# Mic-Breakout_v10.net
KiCad netlist of a schematic drawn in EAGLE
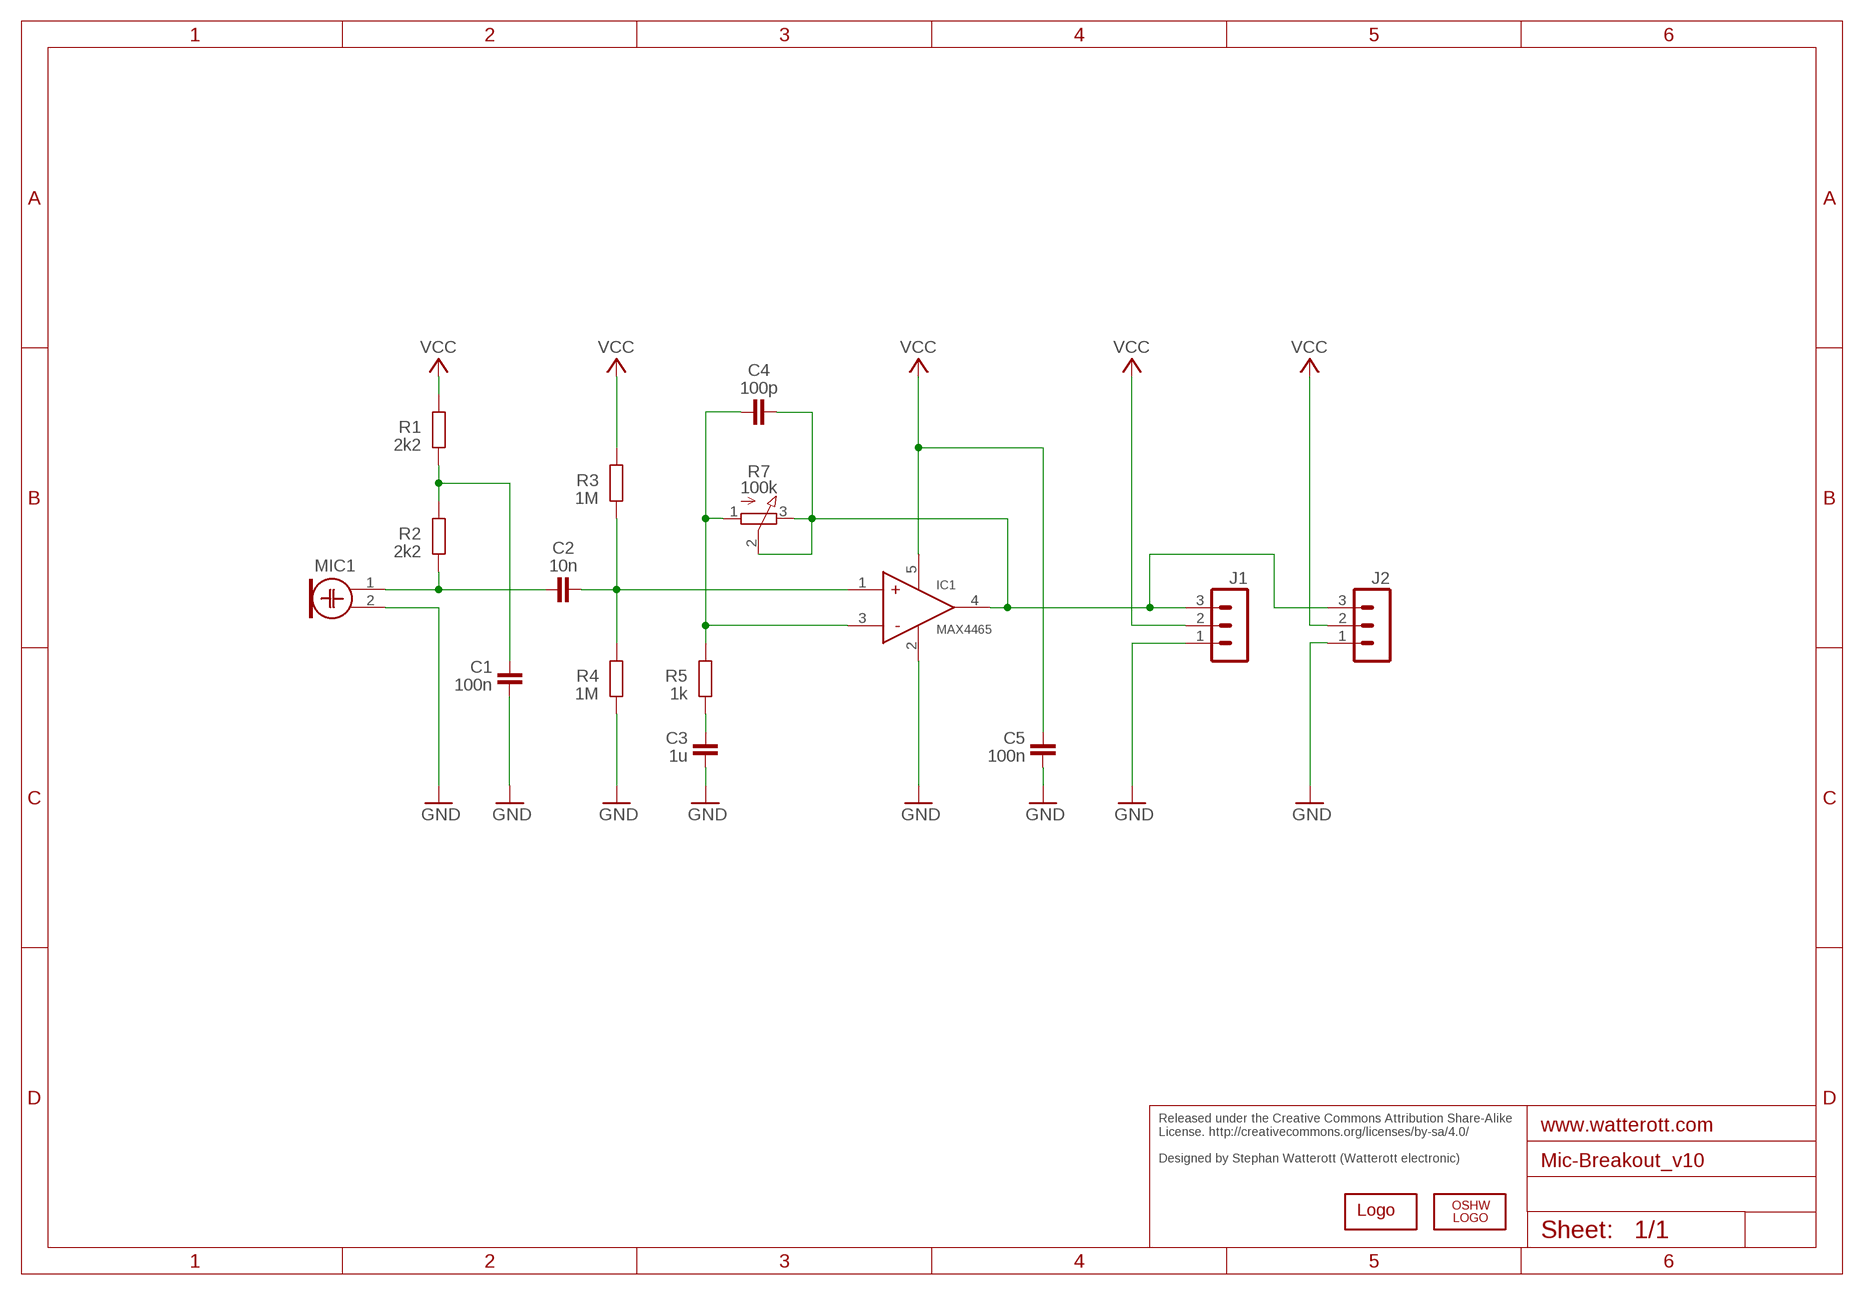
[diagram p0: schematic, sheet 1]

(export (version "E")
  (design (tool "Eeschema 10.0.6"))
  (components
    (comp (ref "C1")
      (value "100n")
      (footprint "eagle-import:R0402")
      (libsource (lib "eagle-import") (part "CAPACITOR-C0402"))
    )
    (comp (ref "C2")
      (value "10n")
      (footprint "eagle-import:R0402")
      (libsource (lib "eagle-import") (part "CAPACITOR-C0402"))
    )
    (comp (ref "C3")
      (value "1u")
      (footprint "eagle-import:R0402")
      (libsource (lib "eagle-import") (part "CAPACITOR-C0402"))
    )
    (comp (ref "C4")
      (value "100p")
      (footprint "eagle-import:R0402")
      (libsource (lib "eagle-import") (part "CAPACITOR-C0402"))
    )
    (comp (ref "C5")
      (value "100n")
      (footprint "eagle-import:R0402")
      (libsource (lib "eagle-import") (part "CAPACITOR-C0402"))
    )
    (comp (ref "IC1")
      (value "MAX4465")
      (footprint "eagle-import:SOT23-5")
      (libsource (lib "eagle-import") (part "MAX4465"))
    )
    (comp (ref "J1")
      (value "MA03-1")
      (footprint "eagle-import:MA03-1")
      (libsource (lib "eagle-import") (part "MA03-1"))
    )
    (comp (ref "J2")
      (value "JST_PH_3S3B-PH-SM4-TB")
      (footprint "eagle-import:JST_S3B-PH-SM4-TB")
      (libsource (lib "eagle-import") (part "JST_PH_3S3B-PH-SM4-TB"))
    )
    (comp (ref "LOGO1")
      (value "LOGO-S_PLACE_M")
      (footprint "eagle-import:SPARK_TPLACE_M")
      (libsource (lib "eagle-import") (part "LOGO-S_PLACE_M"))
    )
    (comp (ref "LOGO2")
      (value "OSHW_LOGOX0100")
      (footprint "eagle-import:OSHW_6X100")
      (libsource (lib "eagle-import") (part "OSHW_LOGOX0100"))
    )
    (comp (ref "MIC1")
      (value "CMA-4544PF")
      (footprint "eagle-import:CMA-4544PF")
      (libsource (lib "eagle-import") (part "CMA-4544PF"))
    )
    (comp (ref "R1")
      (value "2k2")
      (footprint "eagle-import:R0402")
      (libsource (lib "eagle-import") (part "RESISTOR-R0402"))
    )
    (comp (ref "R2")
      (value "2k2")
      (footprint "eagle-import:R0402")
      (libsource (lib "eagle-import") (part "RESISTOR-R0402"))
    )
    (comp (ref "R3")
      (value "1M")
      (footprint "eagle-import:R0402")
      (libsource (lib "eagle-import") (part "RESISTOR-R0402"))
    )
    (comp (ref "R4")
      (value "1M")
      (footprint "eagle-import:R0402")
      (libsource (lib "eagle-import") (part "RESISTOR-R0402"))
    )
    (comp (ref "R5")
      (value "1k")
      (footprint "eagle-import:R0402")
      (libsource (lib "eagle-import") (part "RESISTOR-R0402"))
    )
    (comp (ref "R7")
      (value "100k")
      (footprint "eagle-import:POT_EVM3Y")
      (libsource (lib "eagle-import") (part "POTEVM3Y"))
    )
  )
  (nets
    (net (code "1") (name "GND") (class "Default")
      (node (ref "C1") (pin "1") (pinfunction "1_1") (pintype "passive"))
      (node (ref "C3") (pin "1") (pinfunction "1_1") (pintype "passive"))
      (node (ref "C5") (pin "1") (pinfunction "1_1") (pintype "passive"))
      (node (ref "IC1") (pin "2") (pinfunction "GND_2") (pintype "power_in"))
      (node (ref "J1") (pin "1") (pinfunction "1_1") (pintype "passive"))
      (node (ref "J2") (pin "1") (pinfunction "1_1") (pintype "passive"))
      (node (ref "MIC1") (pin "2") (pinfunction "2_2") (pintype "passive"))
      (node (ref "R4") (pin "1") (pinfunction "1_1") (pintype "passive"))
    )
    (net (code "2") (name "Net-(C1-Pad2)") (class "Default")
      (node (ref "C1") (pin "2") (pinfunction "2_2") (pintype "passive"))
      (node (ref "R1") (pin "1") (pinfunction "1_1") (pintype "passive"))
      (node (ref "R2") (pin "2") (pinfunction "2_2") (pintype "passive"))
    )
    (net (code "3") (name "Net-(C2-Pad1)") (class "Default")
      (node (ref "C2") (pin "1") (pinfunction "1_1") (pintype "passive"))
      (node (ref "MIC1") (pin "1") (pinfunction "1_1") (pintype "passive"))
      (node (ref "R2") (pin "1") (pinfunction "1_1") (pintype "passive"))
    )
    (net (code "4") (name "Net-(C3-Pad2)") (class "Default")
      (node (ref "C3") (pin "2") (pinfunction "2_2") (pintype "passive"))
      (node (ref "R5") (pin "1") (pinfunction "1_1") (pintype "passive"))
    )
    (net (code "5") (name "Net-(IC1-+)") (class "Default")
      (node (ref "C2") (pin "2") (pinfunction "2_2") (pintype "passive"))
      (node (ref "IC1") (pin "1") (pinfunction "+_1") (pintype "input"))
      (node (ref "R3") (pin "1") (pinfunction "1_1") (pintype "passive"))
      (node (ref "R4") (pin "2") (pinfunction "2_2") (pintype "passive"))
    )
    (net (code "6") (name "Net-(IC1--)") (class "Default")
      (node (ref "C4") (pin "2") (pinfunction "2_2") (pintype "passive"))
      (node (ref "IC1") (pin "3") (pinfunction "-_3") (pintype "input"))
      (node (ref "R5") (pin "2") (pinfunction "2_2") (pintype "passive"))
      (node (ref "R7") (pin "1") (pinfunction "A_1") (pintype "passive"))
    )
    (net (code "7") (name "Net-(IC1-OUT)") (class "Default")
      (node (ref "C4") (pin "1") (pinfunction "1_1") (pintype "passive"))
      (node (ref "IC1") (pin "4") (pinfunction "OUT_4") (pintype "output"))
      (node (ref "J1") (pin "3") (pinfunction "3_3") (pintype "passive"))
      (node (ref "J2") (pin "3") (pinfunction "3_3") (pintype "passive"))
      (node (ref "R7") (pin "2") (pinfunction "S_2") (pintype "passive"))
      (node (ref "R7") (pin "3") (pinfunction "E_3") (pintype "passive"))
    )
    (net (code "8") (name "VCC") (class "Default")
      (node (ref "C5") (pin "2") (pinfunction "2_2") (pintype "passive"))
      (node (ref "IC1") (pin "5") (pinfunction "VCC_5") (pintype "power_in"))
      (node (ref "J1") (pin "2") (pinfunction "2_2") (pintype "passive"))
      (node (ref "J2") (pin "2") (pinfunction "2_2") (pintype "passive"))
      (node (ref "R1") (pin "2") (pinfunction "2_2") (pintype "passive"))
      (node (ref "R3") (pin "2") (pinfunction "2_2") (pintype "passive"))
    )
  )
)
